# X15-ESC-Adapter.net
KiCad netlist of a schematic drawn in EAGLE
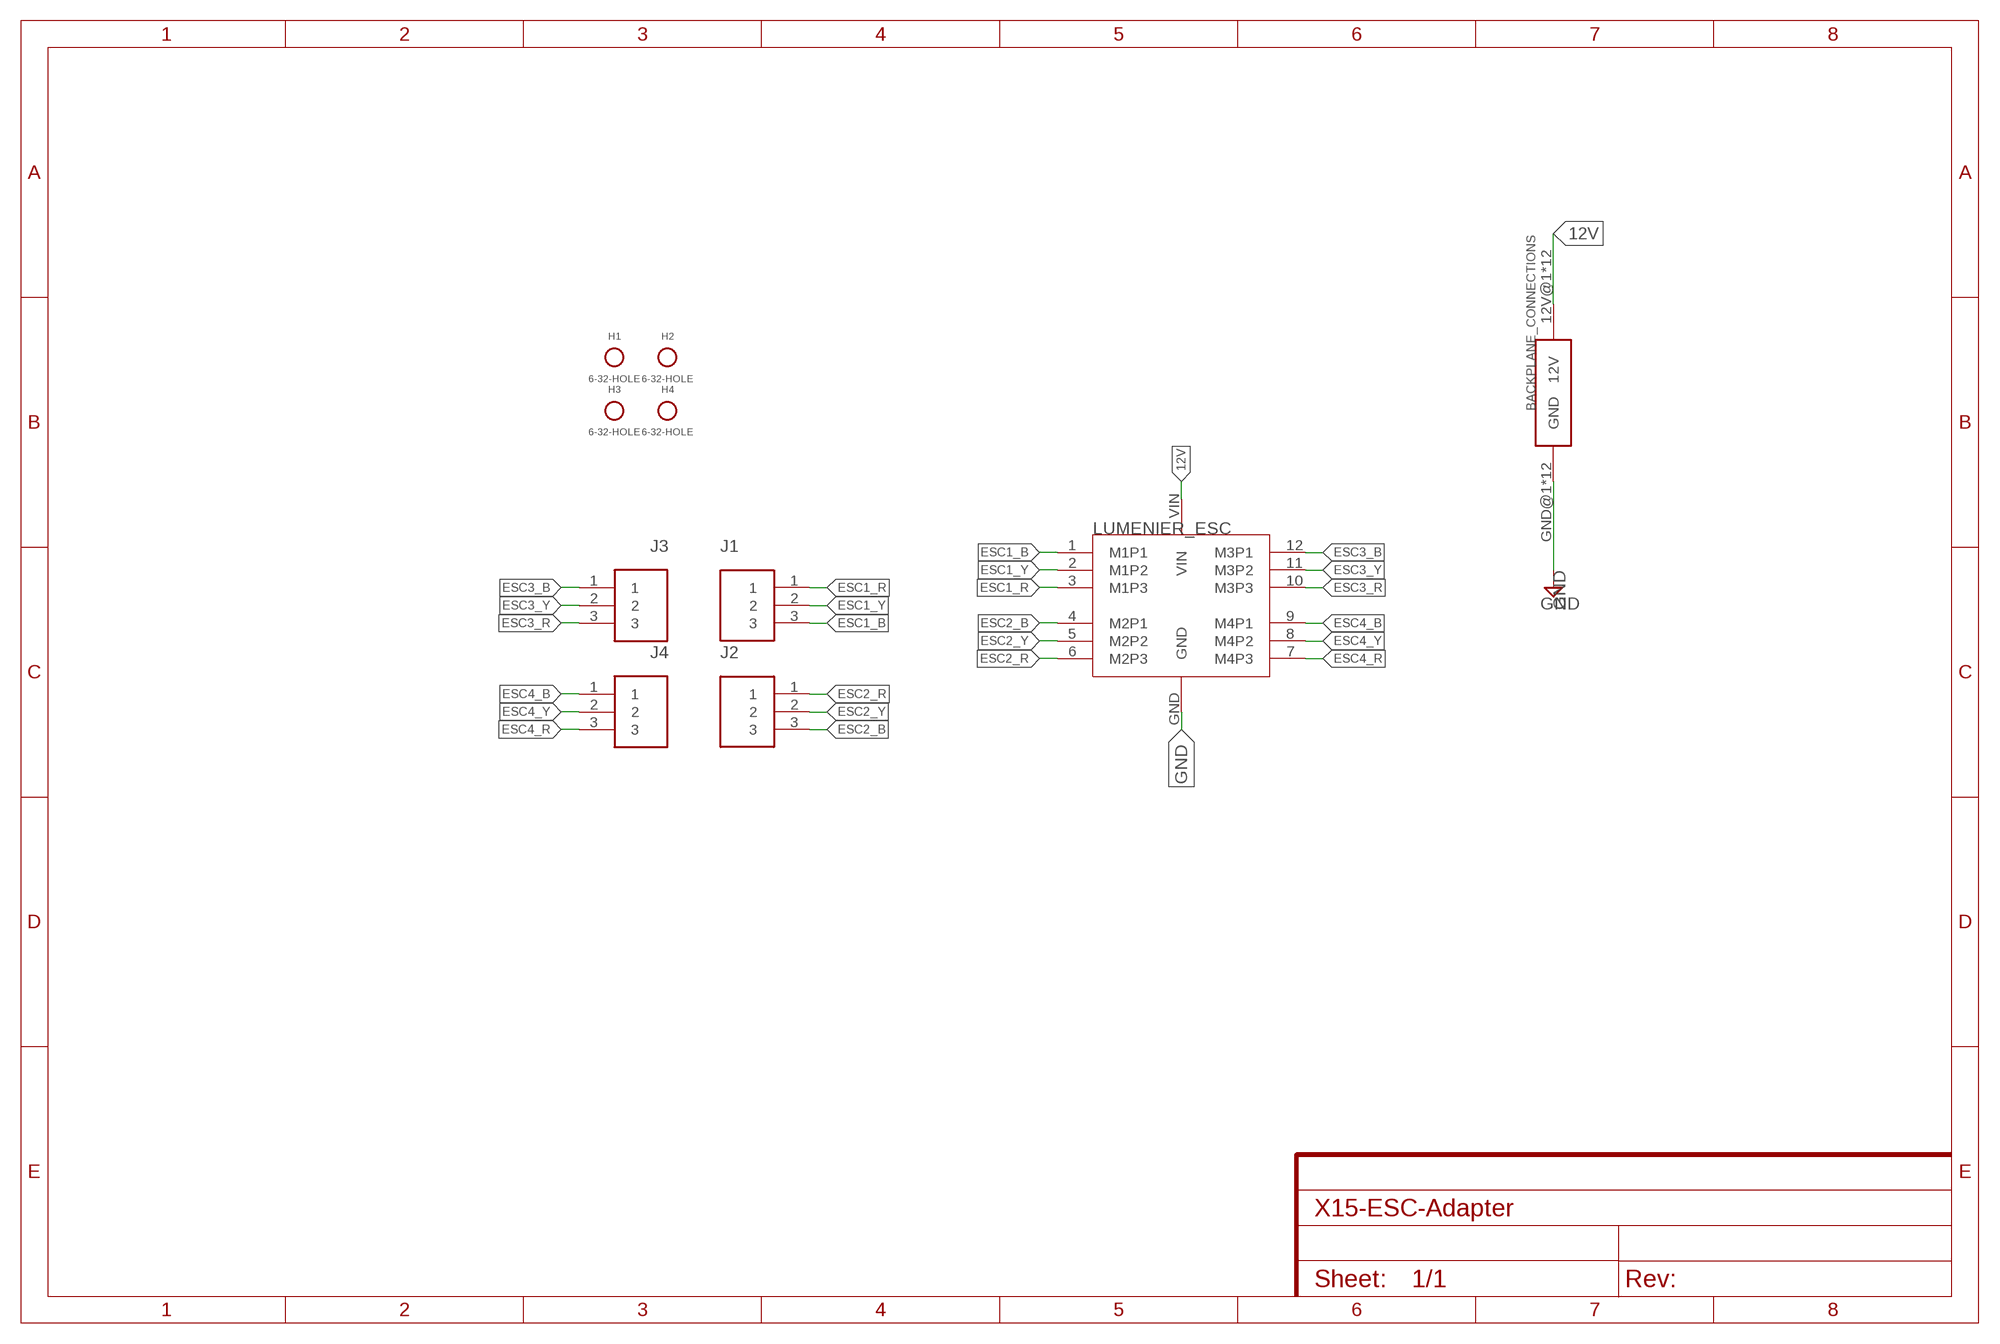
[diagram p0: schematic, sheet 1]

(export (version "E")
  (design (tool "Eeschema 10.0.6"))
  (components
    (comp (ref "BACKPLANE_CONNECTIONS")
      (value "IPS1-112-01-L-D")
      (footprint "eagle-import:IPS1-BACKPLANE_ESC_ADAPTER_ESC_PWR")
      (libsource (lib "eagle-import") (part "IPS1-112-01-L-D"))
    )
    (comp (ref "H1")
      (value "6-32-HOLE")
      (footprint "eagle-import:6-32-HOLE")
      (libsource (lib "eagle-import") (part "6-32-HOLE"))
    )
    (comp (ref "H2")
      (value "6-32-HOLE")
      (footprint "eagle-import:6-32-HOLE")
      (libsource (lib "eagle-import") (part "6-32-HOLE"))
    )
    (comp (ref "H3")
      (value "6-32-HOLE")
      (footprint "eagle-import:6-32-HOLE")
      (libsource (lib "eagle-import") (part "6-32-HOLE"))
    )
    (comp (ref "H4")
      (value "6-32-HOLE")
      (footprint "eagle-import:6-32-HOLE")
      (libsource (lib "eagle-import") (part "6-32-HOLE"))
    )
    (comp (ref "J1")
      (value "IBPT-103-H1-T-S-RA")
      (footprint "eagle-import:IPBT-103-H1-T-S-RA")
      (libsource (lib "eagle-import") (part "IBPT-103-H1-T-S-RA"))
    )
    (comp (ref "J2")
      (value "IBPT-103-H1-T-S-RA")
      (footprint "eagle-import:IPBT-103-H1-T-S-RA")
      (libsource (lib "eagle-import") (part "IBPT-103-H1-T-S-RA"))
    )
    (comp (ref "J3")
      (value "IBPT-103-H1-T-S-RA")
      (footprint "eagle-import:IPBT-103-H1-T-S-RA")
      (libsource (lib "eagle-import") (part "IBPT-103-H1-T-S-RA"))
    )
    (comp (ref "J4")
      (value "IBPT-103-H1-T-S-RA")
      (footprint "eagle-import:IPBT-103-H1-T-S-RA")
      (libsource (lib "eagle-import") (part "IBPT-103-H1-T-S-RA"))
    )
    (comp (ref "LUMENIER_ESC")
      (value "LUMENIER")
      (footprint "eagle-import:LUMENIER")
      (libsource (lib "eagle-import") (part "LUMENIER"))
    )
  )
  (nets
    (net (code "1") (name "12V") (class "Default")
      (node (ref "BACKPLANE_CONNECTIONS") (pin "12V@1") (pinfunction "12V_12V@1") (pintype "bidirectional"))
      (node (ref "BACKPLANE_CONNECTIONS") (pin "12V@10") (pinfunction "12V_12V@10") (pintype "bidirectional"))
      (node (ref "BACKPLANE_CONNECTIONS") (pin "12V@11") (pinfunction "12V_12V@11") (pintype "bidirectional"))
      (node (ref "BACKPLANE_CONNECTIONS") (pin "12V@12") (pinfunction "12V_12V@12") (pintype "bidirectional"))
      (node (ref "BACKPLANE_CONNECTIONS") (pin "12V@2") (pinfunction "12V_12V@2") (pintype "bidirectional"))
      (node (ref "BACKPLANE_CONNECTIONS") (pin "12V@3") (pinfunction "12V_12V@3") (pintype "bidirectional"))
      (node (ref "BACKPLANE_CONNECTIONS") (pin "12V@4") (pinfunction "12V_12V@4") (pintype "bidirectional"))
      (node (ref "BACKPLANE_CONNECTIONS") (pin "12V@5") (pinfunction "12V_12V@5") (pintype "bidirectional"))
      (node (ref "BACKPLANE_CONNECTIONS") (pin "12V@6") (pinfunction "12V_12V@6") (pintype "bidirectional"))
      (node (ref "BACKPLANE_CONNECTIONS") (pin "12V@7") (pinfunction "12V_12V@7") (pintype "bidirectional"))
      (node (ref "BACKPLANE_CONNECTIONS") (pin "12V@8") (pinfunction "12V_12V@8") (pintype "bidirectional"))
      (node (ref "BACKPLANE_CONNECTIONS") (pin "12V@9") (pinfunction "12V_12V@9") (pintype "bidirectional"))
      (node (ref "LUMENIER_ESC") (pin "VIN") (pinfunction "VIN_VIN") (pintype "bidirectional"))
    )
    (net (code "2") (name "ESC1_B") (class "Default")
      (node (ref "J1") (pin "3") (pinfunction "3_3") (pintype "bidirectional"))
      (node (ref "LUMENIER_ESC") (pin "1") (pinfunction "M1P1_1") (pintype "bidirectional"))
    )
    (net (code "3") (name "ESC1_R") (class "Default")
      (node (ref "J1") (pin "1") (pinfunction "1_1") (pintype "bidirectional"))
      (node (ref "LUMENIER_ESC") (pin "3") (pinfunction "M1P3_3") (pintype "bidirectional"))
    )
    (net (code "4") (name "ESC1_Y") (class "Default")
      (node (ref "J1") (pin "2") (pinfunction "2_2") (pintype "bidirectional"))
      (node (ref "LUMENIER_ESC") (pin "2") (pinfunction "M1P2_2") (pintype "bidirectional"))
    )
    (net (code "5") (name "ESC2_B") (class "Default")
      (node (ref "J2") (pin "3") (pinfunction "3_3") (pintype "bidirectional"))
      (node (ref "LUMENIER_ESC") (pin "4") (pinfunction "M2P1_4") (pintype "bidirectional"))
    )
    (net (code "6") (name "ESC2_R") (class "Default")
      (node (ref "J2") (pin "1") (pinfunction "1_1") (pintype "bidirectional"))
      (node (ref "LUMENIER_ESC") (pin "6") (pinfunction "M2P3_6") (pintype "bidirectional"))
    )
    (net (code "7") (name "ESC2_Y") (class "Default")
      (node (ref "J2") (pin "2") (pinfunction "2_2") (pintype "bidirectional"))
      (node (ref "LUMENIER_ESC") (pin "5") (pinfunction "M2P2_5") (pintype "bidirectional"))
    )
    (net (code "8") (name "ESC3_B") (class "Default")
      (node (ref "J3") (pin "1") (pinfunction "1_1") (pintype "bidirectional"))
      (node (ref "LUMENIER_ESC") (pin "12") (pinfunction "M3P1_12") (pintype "bidirectional"))
    )
    (net (code "9") (name "ESC3_R") (class "Default")
      (node (ref "J3") (pin "3") (pinfunction "3_3") (pintype "bidirectional"))
      (node (ref "LUMENIER_ESC") (pin "10") (pinfunction "M3P3_10") (pintype "bidirectional"))
    )
    (net (code "10") (name "ESC3_Y") (class "Default")
      (node (ref "J3") (pin "2") (pinfunction "2_2") (pintype "bidirectional"))
      (node (ref "LUMENIER_ESC") (pin "11") (pinfunction "M3P2_11") (pintype "bidirectional"))
    )
    (net (code "11") (name "ESC4_B") (class "Default")
      (node (ref "J4") (pin "1") (pinfunction "1_1") (pintype "bidirectional"))
      (node (ref "LUMENIER_ESC") (pin "9") (pinfunction "M4P1_9") (pintype "bidirectional"))
    )
    (net (code "12") (name "ESC4_R") (class "Default")
      (node (ref "J4") (pin "3") (pinfunction "3_3") (pintype "bidirectional"))
      (node (ref "LUMENIER_ESC") (pin "7") (pinfunction "M4P3_7") (pintype "bidirectional"))
    )
    (net (code "13") (name "ESC4_Y") (class "Default")
      (node (ref "J4") (pin "2") (pinfunction "2_2") (pintype "bidirectional"))
      (node (ref "LUMENIER_ESC") (pin "8") (pinfunction "M4P2_8") (pintype "bidirectional"))
    )
    (net (code "14") (name "GND") (class "Default")
      (node (ref "BACKPLANE_CONNECTIONS") (pin "GND@1") (pinfunction "GND_GND@1") (pintype "bidirectional"))
      (node (ref "BACKPLANE_CONNECTIONS") (pin "GND@10") (pinfunction "GND_GND@10") (pintype "bidirectional"))
      (node (ref "BACKPLANE_CONNECTIONS") (pin "GND@11") (pinfunction "GND_GND@11") (pintype "bidirectional"))
      (node (ref "BACKPLANE_CONNECTIONS") (pin "GND@12") (pinfunction "GND_GND@12") (pintype "bidirectional"))
      (node (ref "BACKPLANE_CONNECTIONS") (pin "GND@2") (pinfunction "GND_GND@2") (pintype "bidirectional"))
      (node (ref "BACKPLANE_CONNECTIONS") (pin "GND@3") (pinfunction "GND_GND@3") (pintype "bidirectional"))
      (node (ref "BACKPLANE_CONNECTIONS") (pin "GND@4") (pinfunction "GND_GND@4") (pintype "bidirectional"))
      (node (ref "BACKPLANE_CONNECTIONS") (pin "GND@5") (pinfunction "GND_GND@5") (pintype "bidirectional"))
      (node (ref "BACKPLANE_CONNECTIONS") (pin "GND@6") (pinfunction "GND_GND@6") (pintype "bidirectional"))
      (node (ref "BACKPLANE_CONNECTIONS") (pin "GND@7") (pinfunction "GND_GND@7") (pintype "bidirectional"))
      (node (ref "BACKPLANE_CONNECTIONS") (pin "GND@8") (pinfunction "GND_GND@8") (pintype "bidirectional"))
      (node (ref "BACKPLANE_CONNECTIONS") (pin "GND@9") (pinfunction "GND_GND@9") (pintype "bidirectional"))
      (node (ref "LUMENIER_ESC") (pin "GND") (pinfunction "GND_GND") (pintype "bidirectional"))
    )
  )
)
